# Teeces_PSI.net
KiCad netlist of a schematic drawn in EAGLE
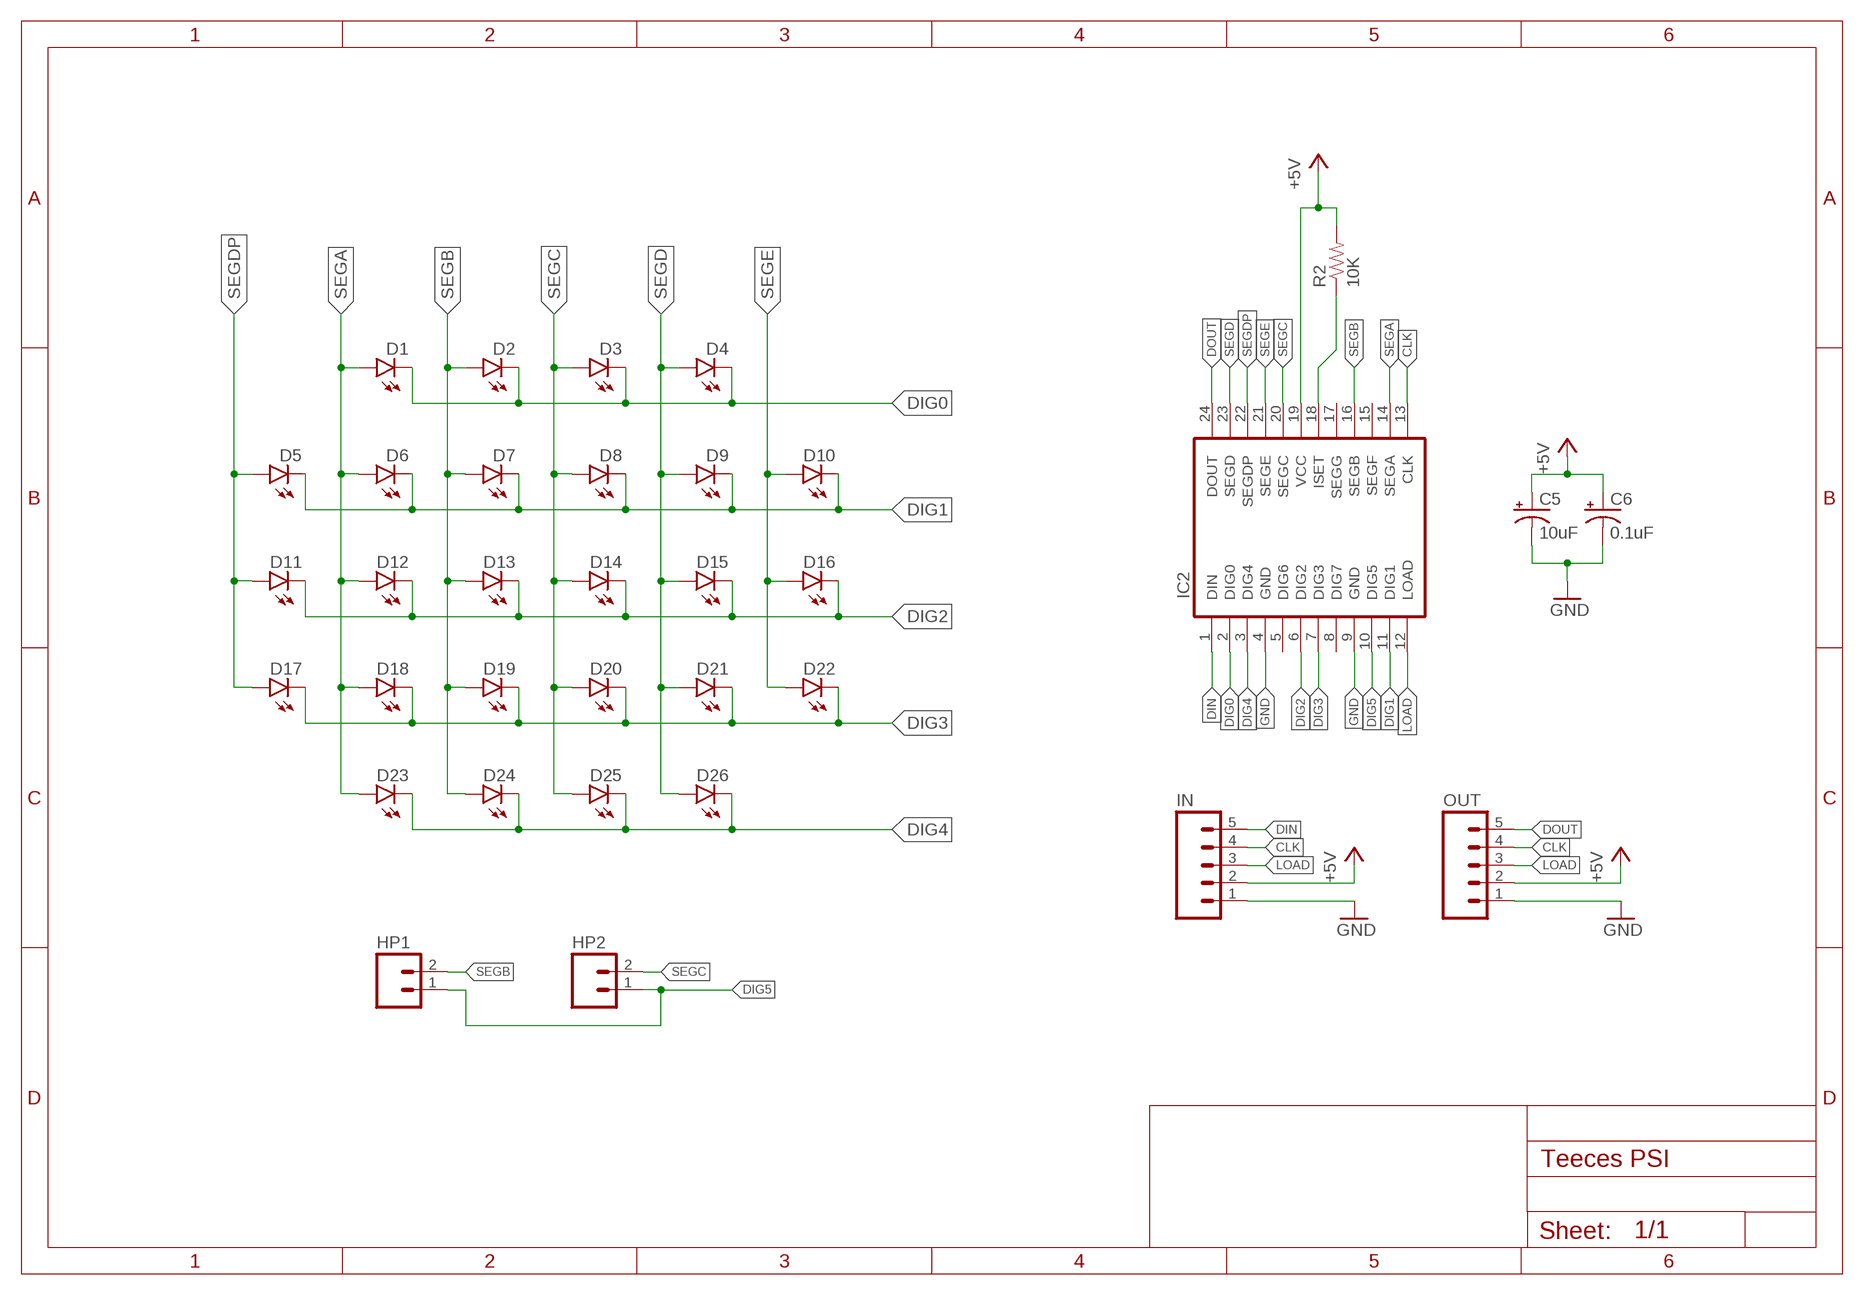
[diagram p0: schematic, sheet 1]

(export (version "E")
  (design (tool "Eeschema 10.0.6"))
  (components
    (comp (ref "C5")
      (value "10uF")
      (footprint "eagle-import:E2,5-5")
      (libsource (lib "eagle-import") (part "CPOL-USE2.5-5"))
    )
    (comp (ref "C6")
      (value "0.1uF")
      (footprint "eagle-import:E2,5-5")
      (libsource (lib "eagle-import") (part "CPOL-USE2.5-5"))
    )
    (comp (ref "D1")
      (value "LED5MM")
      (footprint "eagle-import:LED5MM_SLIM")
      (libsource (lib "eagle-import") (part "LED5MM"))
    )
    (comp (ref "D2")
      (value "LED5MM")
      (footprint "eagle-import:LED5MM_SLIM")
      (libsource (lib "eagle-import") (part "LED5MM"))
    )
    (comp (ref "D3")
      (value "LED5MM")
      (footprint "eagle-import:LED5MM_SLIM")
      (libsource (lib "eagle-import") (part "LED5MM"))
    )
    (comp (ref "D4")
      (value "LED5MM")
      (footprint "eagle-import:LED5MM_SLIM")
      (libsource (lib "eagle-import") (part "LED5MM"))
    )
    (comp (ref "D5")
      (value "LED5MM")
      (footprint "eagle-import:LED5MM_SLIM")
      (libsource (lib "eagle-import") (part "LED5MM"))
    )
    (comp (ref "D6")
      (value "LED5MM")
      (footprint "eagle-import:LED5MM_SLIM")
      (libsource (lib "eagle-import") (part "LED5MM"))
    )
    (comp (ref "D7")
      (value "LED5MM")
      (footprint "eagle-import:LED5MM_SLIM")
      (libsource (lib "eagle-import") (part "LED5MM"))
    )
    (comp (ref "D8")
      (value "LED5MM")
      (footprint "eagle-import:LED5MM_SLIM")
      (libsource (lib "eagle-import") (part "LED5MM"))
    )
    (comp (ref "D9")
      (value "LED5MM")
      (footprint "eagle-import:LED5MM_SLIM")
      (libsource (lib "eagle-import") (part "LED5MM"))
    )
    (comp (ref "D10")
      (value "LED5MM")
      (footprint "eagle-import:LED5MM_SLIM")
      (libsource (lib "eagle-import") (part "LED5MM"))
    )
    (comp (ref "D11")
      (value "LED5MM")
      (footprint "eagle-import:LED5MM_SLIM")
      (libsource (lib "eagle-import") (part "LED5MM"))
    )
    (comp (ref "D12")
      (value "LED5MM")
      (footprint "eagle-import:LED5MM_SLIM")
      (libsource (lib "eagle-import") (part "LED5MM"))
    )
    (comp (ref "D13")
      (value "LED5MM")
      (footprint "eagle-import:LED5MM_SLIM")
      (libsource (lib "eagle-import") (part "LED5MM"))
    )
    (comp (ref "D14")
      (value "LED5MM")
      (footprint "eagle-import:LED5MM_SLIM")
      (libsource (lib "eagle-import") (part "LED5MM"))
    )
    (comp (ref "D15")
      (value "LED5MM")
      (footprint "eagle-import:LED5MM_SLIM")
      (libsource (lib "eagle-import") (part "LED5MM"))
    )
    (comp (ref "D16")
      (value "LED5MM")
      (footprint "eagle-import:LED5MM_SLIM")
      (libsource (lib "eagle-import") (part "LED5MM"))
    )
    (comp (ref "D17")
      (value "LED5MM")
      (footprint "eagle-import:LED5MM_SLIM")
      (libsource (lib "eagle-import") (part "LED5MM"))
    )
    (comp (ref "D18")
      (value "LED5MM")
      (footprint "eagle-import:LED5MM_SLIM")
      (libsource (lib "eagle-import") (part "LED5MM"))
    )
    (comp (ref "D19")
      (value "LED5MM")
      (footprint "eagle-import:LED5MM_SLIM")
      (libsource (lib "eagle-import") (part "LED5MM"))
    )
    (comp (ref "D20")
      (value "LED5MM")
      (footprint "eagle-import:LED5MM_SLIM")
      (libsource (lib "eagle-import") (part "LED5MM"))
    )
    (comp (ref "D21")
      (value "LED5MM")
      (footprint "eagle-import:LED5MM_SLIM")
      (libsource (lib "eagle-import") (part "LED5MM"))
    )
    (comp (ref "D22")
      (value "LED5MM")
      (footprint "eagle-import:LED5MM_SLIM")
      (libsource (lib "eagle-import") (part "LED5MM"))
    )
    (comp (ref "D23")
      (value "LED5MM")
      (footprint "eagle-import:LED5MM_SLIM")
      (libsource (lib "eagle-import") (part "LED5MM"))
    )
    (comp (ref "D24")
      (value "LED5MM")
      (footprint "eagle-import:LED5MM_SLIM")
      (libsource (lib "eagle-import") (part "LED5MM"))
    )
    (comp (ref "D25")
      (value "LED5MM")
      (footprint "eagle-import:LED5MM_SLIM")
      (libsource (lib "eagle-import") (part "LED5MM"))
    )
    (comp (ref "D26")
      (value "LED5MM")
      (footprint "eagle-import:LED5MM_SLIM")
      (libsource (lib "eagle-import") (part "LED5MM"))
    )
    (comp (ref "HP1")
      (value "M02SQ")
      (footprint "eagle-import:1X02-SQ")
      (libsource (lib "eagle-import") (part "M02SQ"))
    )
    (comp (ref "HP2")
      (value "M02SQ")
      (footprint "eagle-import:1X02-SQ")
      (libsource (lib "eagle-import") (part "M02SQ"))
    )
    (comp (ref "IC2")
      (value "MAX7219CNG")
      (footprint "eagle-import:DIP24-3")
      (libsource (lib "eagle-import") (part "MAX7219CNGROUNDPADS"))
    )
    (comp (ref "IN")
      (value "CONN_05")
      (footprint "eagle-import:1X05")
      (libsource (lib "eagle-import") (part "CONN_05"))
    )
    (comp (ref "OUT")
      (value "CONN_05")
      (footprint "eagle-import:1X05")
      (libsource (lib "eagle-import") (part "CONN_05"))
    )
    (comp (ref "R2")
      (value "10K")
      (footprint "eagle-import:AXIAL-0.3")
      (libsource (lib "eagle-import") (part "RESISTORAXIAL-0.3"))
    )
  )
  (nets
    (net (code "1") (name "+5V") (class "Default")
      (node (ref "C5") (pin "+") (pinfunction "+_+") (pintype "passive"))
      (node (ref "C6") (pin "+") (pinfunction "+_+") (pintype "passive"))
      (node (ref "IC2") (pin "19") (pinfunction "VCC_19") (pintype "power_in"))
      (node (ref "IN") (pin "2") (pinfunction "2_2") (pintype "passive"))
      (node (ref "OUT") (pin "2") (pinfunction "2_2") (pintype "passive"))
      (node (ref "R2") (pin "P$2") (pinfunction "2_P$2") (pintype "passive"))
    )
    (net (code "2") (name "CLK") (class "Default")
      (node (ref "IC2") (pin "13") (pinfunction "CLK_13") (pintype "output"))
      (node (ref "IN") (pin "4") (pinfunction "4_4") (pintype "passive"))
      (node (ref "OUT") (pin "4") (pinfunction "4_4") (pintype "passive"))
    )
    (net (code "3") (name "DIG0") (class "Default")
      (node (ref "D1") (pin "K") (pinfunction "C_K") (pintype "passive"))
      (node (ref "D2") (pin "K") (pinfunction "C_K") (pintype "passive"))
      (node (ref "D3") (pin "K") (pinfunction "C_K") (pintype "passive"))
      (node (ref "D4") (pin "K") (pinfunction "C_K") (pintype "passive"))
      (node (ref "IC2") (pin "2") (pinfunction "DIG0_2") (pintype "output"))
    )
    (net (code "4") (name "DIG1") (class "Default")
      (node (ref "D10") (pin "K") (pinfunction "C_K") (pintype "passive"))
      (node (ref "D5") (pin "K") (pinfunction "C_K") (pintype "passive"))
      (node (ref "D6") (pin "K") (pinfunction "C_K") (pintype "passive"))
      (node (ref "D7") (pin "K") (pinfunction "C_K") (pintype "passive"))
      (node (ref "D8") (pin "K") (pinfunction "C_K") (pintype "passive"))
      (node (ref "D9") (pin "K") (pinfunction "C_K") (pintype "passive"))
      (node (ref "IC2") (pin "11") (pinfunction "DIG1_11") (pintype "output"))
    )
    (net (code "5") (name "DIG2") (class "Default")
      (node (ref "D11") (pin "K") (pinfunction "C_K") (pintype "passive"))
      (node (ref "D12") (pin "K") (pinfunction "C_K") (pintype "passive"))
      (node (ref "D13") (pin "K") (pinfunction "C_K") (pintype "passive"))
      (node (ref "D14") (pin "K") (pinfunction "C_K") (pintype "passive"))
      (node (ref "D15") (pin "K") (pinfunction "C_K") (pintype "passive"))
      (node (ref "D16") (pin "K") (pinfunction "C_K") (pintype "passive"))
      (node (ref "IC2") (pin "6") (pinfunction "DIG2_6") (pintype "output"))
    )
    (net (code "6") (name "DIG3") (class "Default")
      (node (ref "D17") (pin "K") (pinfunction "C_K") (pintype "passive"))
      (node (ref "D18") (pin "K") (pinfunction "C_K") (pintype "passive"))
      (node (ref "D19") (pin "K") (pinfunction "C_K") (pintype "passive"))
      (node (ref "D20") (pin "K") (pinfunction "C_K") (pintype "passive"))
      (node (ref "D21") (pin "K") (pinfunction "C_K") (pintype "passive"))
      (node (ref "D22") (pin "K") (pinfunction "C_K") (pintype "passive"))
      (node (ref "IC2") (pin "7") (pinfunction "DIG3_7") (pintype "output"))
    )
    (net (code "7") (name "DIG4") (class "Default")
      (node (ref "D23") (pin "K") (pinfunction "C_K") (pintype "passive"))
      (node (ref "D24") (pin "K") (pinfunction "C_K") (pintype "passive"))
      (node (ref "D25") (pin "K") (pinfunction "C_K") (pintype "passive"))
      (node (ref "D26") (pin "K") (pinfunction "C_K") (pintype "passive"))
      (node (ref "IC2") (pin "3") (pinfunction "DIG4_3") (pintype "output"))
    )
    (net (code "8") (name "DIG5") (class "Default")
      (node (ref "HP1") (pin "1") (pinfunction "1_1") (pintype "passive"))
      (node (ref "HP2") (pin "1") (pinfunction "1_1") (pintype "passive"))
      (node (ref "IC2") (pin "10") (pinfunction "DIG5_10") (pintype "output"))
    )
    (net (code "9") (name "DIN") (class "Default")
      (node (ref "IC2") (pin "1") (pinfunction "DIN_1") (pintype "input"))
      (node (ref "IN") (pin "5") (pinfunction "5_5") (pintype "passive"))
    )
    (net (code "10") (name "DOUT") (class "Default")
      (node (ref "IC2") (pin "24") (pinfunction "DOUT_24") (pintype "output"))
      (node (ref "OUT") (pin "5") (pinfunction "5_5") (pintype "passive"))
    )
    (net (code "11") (name "GND") (class "Default")
      (node (ref "C5") (pin "-") (pinfunction "-_-") (pintype "passive"))
      (node (ref "C6") (pin "-") (pinfunction "-_-") (pintype "passive"))
      (node (ref "IC2") (pin "4") (pinfunction "GND_4") (pintype "power_in"))
      (node (ref "IC2") (pin "9") (pinfunction "GND_9") (pintype "power_in"))
      (node (ref "IN") (pin "1") (pinfunction "1_1") (pintype "passive"))
      (node (ref "OUT") (pin "1") (pinfunction "1_1") (pintype "passive"))
    )
    (net (code "12") (name "LOAD") (class "Default")
      (node (ref "IC2") (pin "12") (pinfunction "LOAD_12") (pintype "input"))
      (node (ref "IN") (pin "3") (pinfunction "3_3") (pintype "passive"))
      (node (ref "OUT") (pin "3") (pinfunction "3_3") (pintype "passive"))
    )
    (net (code "13") (name "Net-(IC2-ISET)") (class "Default")
      (node (ref "IC2") (pin "18") (pinfunction "ISET_18") (pintype "input"))
      (node (ref "R2") (pin "P$1") (pinfunction "1_P$1") (pintype "passive"))
    )
    (net (code "14") (name "SEGA") (class "Default")
      (node (ref "D1") (pin "A") (pinfunction "A_A") (pintype "passive"))
      (node (ref "D12") (pin "A") (pinfunction "A_A") (pintype "passive"))
      (node (ref "D18") (pin "A") (pinfunction "A_A") (pintype "passive"))
      (node (ref "D23") (pin "A") (pinfunction "A_A") (pintype "passive"))
      (node (ref "D6") (pin "A") (pinfunction "A_A") (pintype "passive"))
      (node (ref "IC2") (pin "14") (pinfunction "SEGA_14") (pintype "output"))
    )
    (net (code "15") (name "SEGB") (class "Default")
      (node (ref "D13") (pin "A") (pinfunction "A_A") (pintype "passive"))
      (node (ref "D19") (pin "A") (pinfunction "A_A") (pintype "passive"))
      (node (ref "D2") (pin "A") (pinfunction "A_A") (pintype "passive"))
      (node (ref "D24") (pin "A") (pinfunction "A_A") (pintype "passive"))
      (node (ref "D7") (pin "A") (pinfunction "A_A") (pintype "passive"))
      (node (ref "HP1") (pin "2") (pinfunction "2_2") (pintype "passive"))
      (node (ref "IC2") (pin "16") (pinfunction "SEGB_16") (pintype "output"))
    )
    (net (code "16") (name "SEGC") (class "Default")
      (node (ref "D14") (pin "A") (pinfunction "A_A") (pintype "passive"))
      (node (ref "D20") (pin "A") (pinfunction "A_A") (pintype "passive"))
      (node (ref "D25") (pin "A") (pinfunction "A_A") (pintype "passive"))
      (node (ref "D3") (pin "A") (pinfunction "A_A") (pintype "passive"))
      (node (ref "D8") (pin "A") (pinfunction "A_A") (pintype "passive"))
      (node (ref "HP2") (pin "2") (pinfunction "2_2") (pintype "passive"))
      (node (ref "IC2") (pin "20") (pinfunction "SEGC_20") (pintype "output"))
    )
    (net (code "17") (name "SEGD") (class "Default")
      (node (ref "D15") (pin "A") (pinfunction "A_A") (pintype "passive"))
      (node (ref "D21") (pin "A") (pinfunction "A_A") (pintype "passive"))
      (node (ref "D26") (pin "A") (pinfunction "A_A") (pintype "passive"))
      (node (ref "D4") (pin "A") (pinfunction "A_A") (pintype "passive"))
      (node (ref "D9") (pin "A") (pinfunction "A_A") (pintype "passive"))
      (node (ref "IC2") (pin "23") (pinfunction "SEGD_23") (pintype "output"))
    )
    (net (code "18") (name "SEGDP") (class "Default")
      (node (ref "D11") (pin "A") (pinfunction "A_A") (pintype "passive"))
      (node (ref "D17") (pin "A") (pinfunction "A_A") (pintype "passive"))
      (node (ref "D5") (pin "A") (pinfunction "A_A") (pintype "passive"))
      (node (ref "IC2") (pin "22") (pinfunction "SEGDP_22") (pintype "output"))
    )
    (net (code "19") (name "SEGE") (class "Default")
      (node (ref "D10") (pin "A") (pinfunction "A_A") (pintype "passive"))
      (node (ref "D16") (pin "A") (pinfunction "A_A") (pintype "passive"))
      (node (ref "D22") (pin "A") (pinfunction "A_A") (pintype "passive"))
      (node (ref "IC2") (pin "21") (pinfunction "SEGE_21") (pintype "output"))
    )
    (net (code "20") (name "unconnected-(IC2-DIG6-Pad5)") (class "Default")
      (node (ref "IC2") (pin "5") (pinfunction "DIG6_5") (pintype "output"))
    )
    (net (code "21") (name "unconnected-(IC2-DIG7-Pad8)") (class "Default")
      (node (ref "IC2") (pin "8") (pinfunction "DIG7_8") (pintype "output"))
    )
    (net (code "22") (name "unconnected-(IC2-SEGF-Pad15)") (class "Default")
      (node (ref "IC2") (pin "15") (pinfunction "SEGF_15") (pintype "output"))
    )
    (net (code "23") (name "unconnected-(IC2-SEGG-Pad17)") (class "Default")
      (node (ref "IC2") (pin "17") (pinfunction "SEGG_17") (pintype "output"))
    )
  )
)
